# nr1.net
KiCad netlist of a schematic drawn in EAGLE
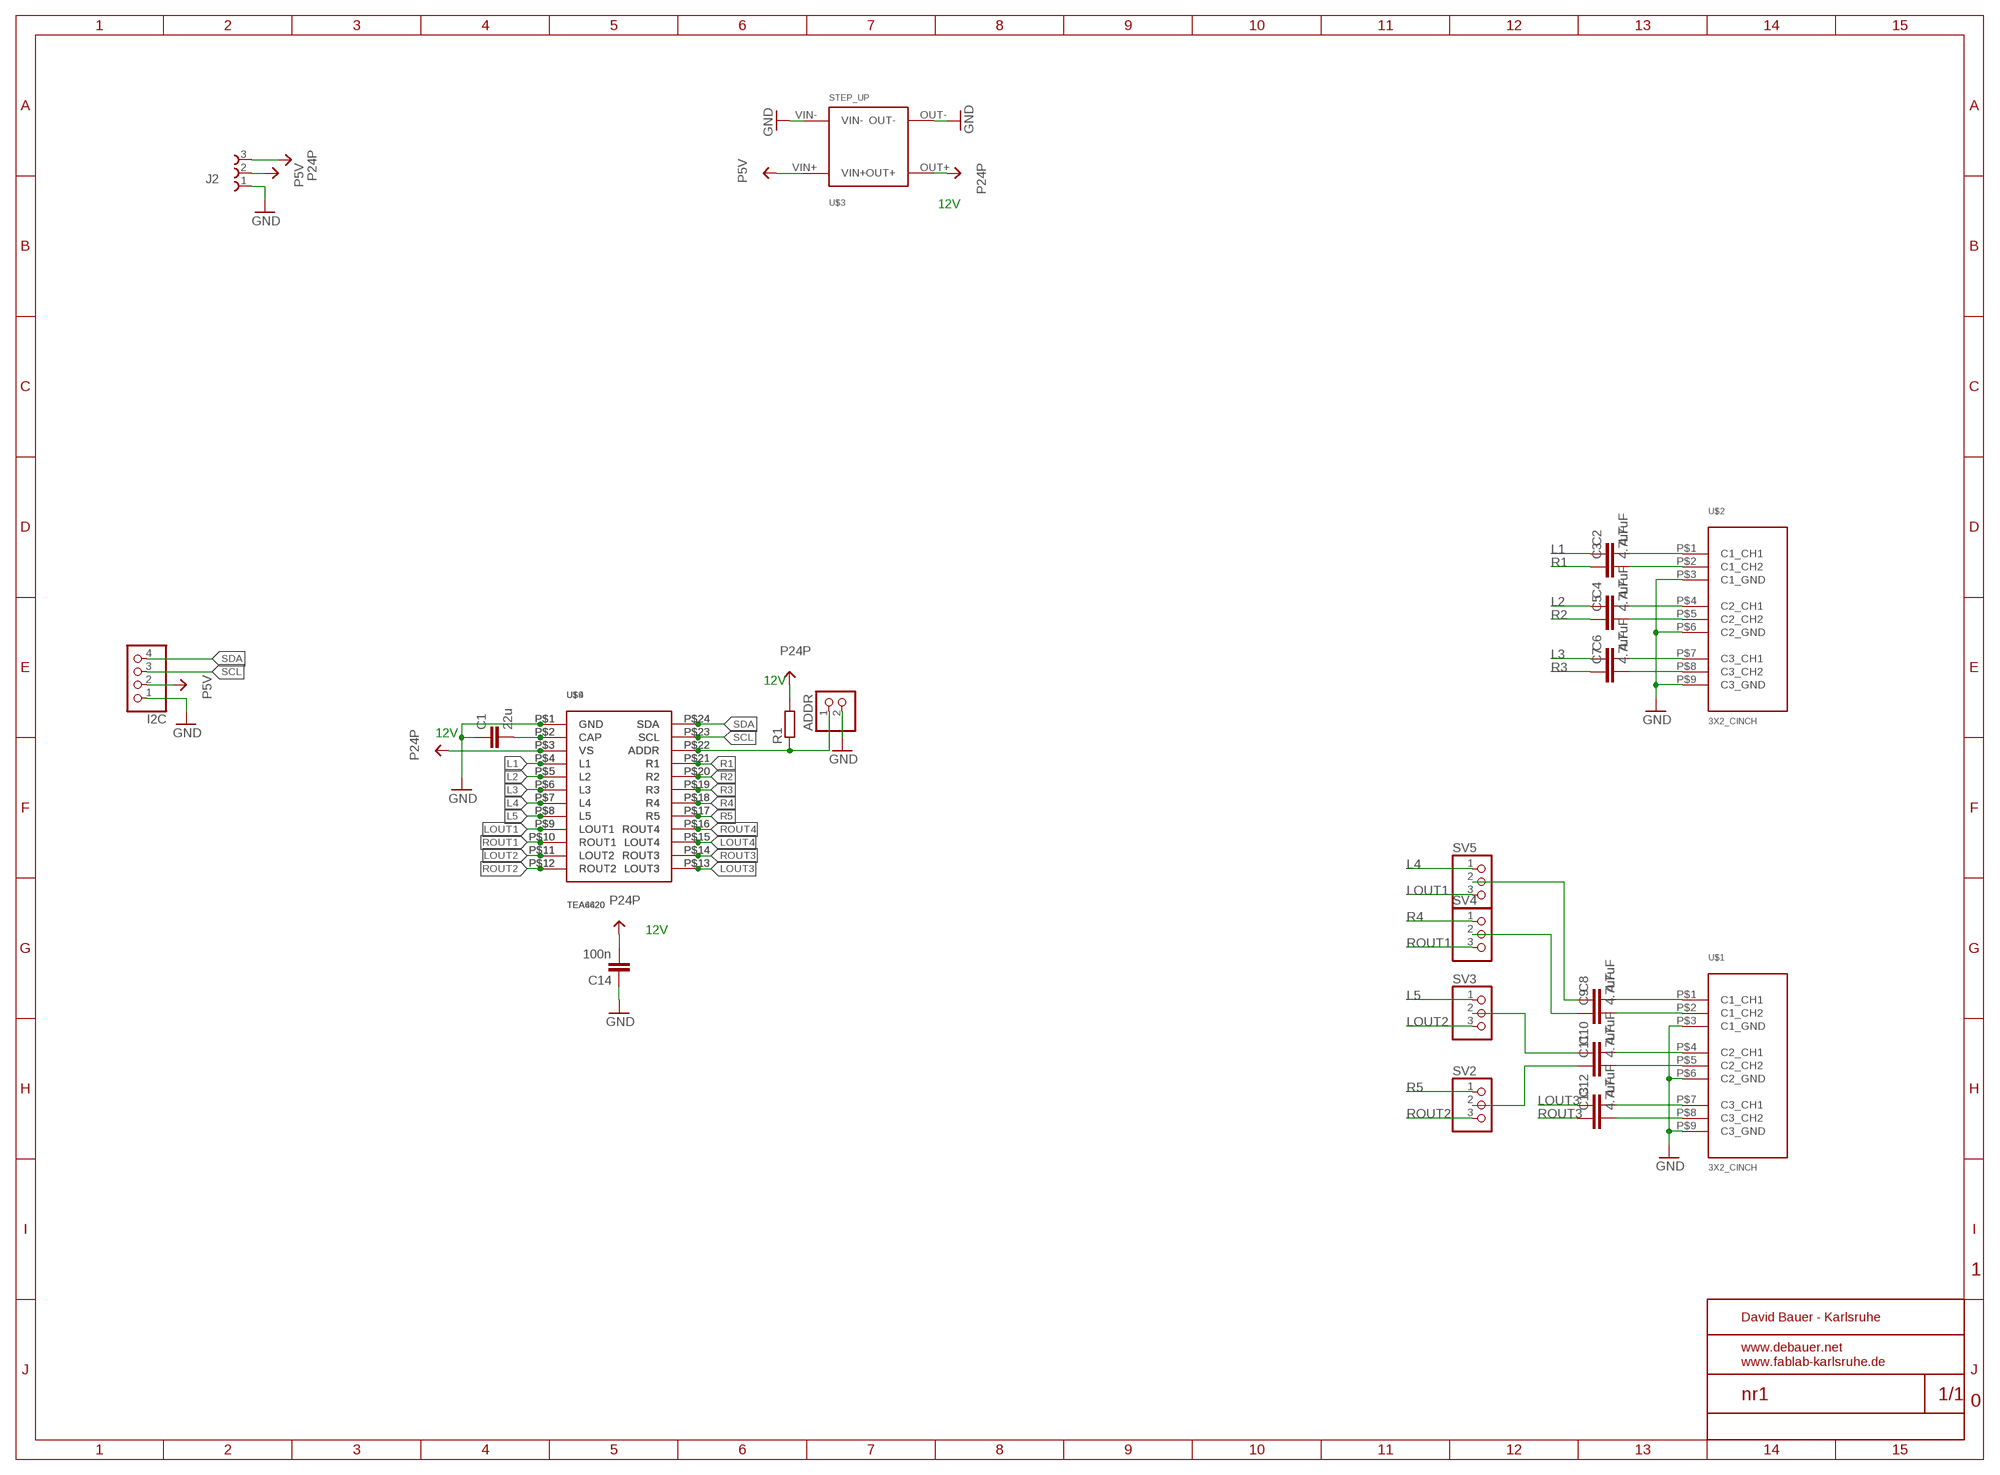
[diagram p0: schematic, sheet 1]

(export (version "E")
  (design (tool "Eeschema 10.0.6"))
  (components
    (comp (ref "ADDR")
      (value "PINHD-1X2")
      (footprint "eagle-import:1X02")
      (libsource (lib "eagle-import") (part "PINHD-1X2"))
    )
    (comp (ref "C1")
      (value "22u")
      (footprint "eagle-import:C0805")
      (libsource (lib "eagle-import") (part "C-EUC0805"))
    )
    (comp (ref "C2")
      (value "4.7uF")
      (footprint "eagle-import:C0805")
      (libsource (lib "eagle-import") (part "C-EUC0805"))
    )
    (comp (ref "C3")
      (value "4.7uF")
      (footprint "eagle-import:C0805")
      (libsource (lib "eagle-import") (part "C-EUC0805"))
    )
    (comp (ref "C4")
      (value "4.7uF")
      (footprint "eagle-import:C0805")
      (libsource (lib "eagle-import") (part "C-EUC0805"))
    )
    (comp (ref "C5")
      (value "4.7uF")
      (footprint "eagle-import:C0805")
      (libsource (lib "eagle-import") (part "C-EUC0805"))
    )
    (comp (ref "C6")
      (value "4.7uF")
      (footprint "eagle-import:C0805")
      (libsource (lib "eagle-import") (part "C-EUC0805"))
    )
    (comp (ref "C7")
      (value "4.7uF")
      (footprint "eagle-import:C0805")
      (libsource (lib "eagle-import") (part "C-EUC0805"))
    )
    (comp (ref "C8")
      (value "4.7uF")
      (footprint "eagle-import:C0805")
      (libsource (lib "eagle-import") (part "C-EUC0805"))
    )
    (comp (ref "C9")
      (value "4.7uF")
      (footprint "eagle-import:C0805")
      (libsource (lib "eagle-import") (part "C-EUC0805"))
    )
    (comp (ref "C10")
      (value "4.7uF")
      (footprint "eagle-import:C0805")
      (libsource (lib "eagle-import") (part "C-EUC0805"))
    )
    (comp (ref "C11")
      (value "4.7uF")
      (footprint "eagle-import:C0805")
      (libsource (lib "eagle-import") (part "C-EUC0805"))
    )
    (comp (ref "C12")
      (value "4.7uF")
      (footprint "eagle-import:C0805")
      (libsource (lib "eagle-import") (part "C-EUC0805"))
    )
    (comp (ref "C13")
      (value "4.7uF")
      (footprint "eagle-import:C0805")
      (libsource (lib "eagle-import") (part "C-EUC0805"))
    )
    (comp (ref "C14")
      (value "100n")
      (footprint "eagle-import:C0805")
      (libsource (lib "eagle-import") (part "C-EUC0805"))
    )
    (comp (ref "I2C")
      (value "PINHD-1X4")
      (footprint "eagle-import:1X04")
      (libsource (lib "eagle-import") (part "PINHD-1X4"))
    )
    (comp (ref "J2")
      (value "691210910003")
      (footprint "eagle-import:691210910003")
      (libsource (lib "eagle-import") (part "691210910003"))
    )
    (comp (ref "R1")
      (value "R-EU_R0805")
      (footprint "eagle-import:R0805")
      (libsource (lib "eagle-import") (part "R-EU_R0805"))
    )
    (comp (ref "SV2")
      (value "PINHD-1X3")
      (footprint "eagle-import:1X03")
      (libsource (lib "eagle-import") (part "PINHD-1X3"))
    )
    (comp (ref "SV3")
      (value "PINHD-1X3")
      (footprint "eagle-import:1X03")
      (libsource (lib "eagle-import") (part "PINHD-1X3"))
    )
    (comp (ref "SV4")
      (value "PINHD-1X3")
      (footprint "eagle-import:1X03")
      (libsource (lib "eagle-import") (part "PINHD-1X3"))
    )
    (comp (ref "SV5")
      (value "PINHD-1X3")
      (footprint "eagle-import:1X03")
      (libsource (lib "eagle-import") (part "PINHD-1X3"))
    )
    (comp (ref "U$1")
      (value "3X2_CINCH")
      (footprint "eagle-import:3X2_CINCH")
      (libsource (lib "eagle-import") (part "3X2_CINCH"))
    )
    (comp (ref "U$2")
      (value "3X2_CINCH")
      (footprint "eagle-import:3X2_CINCH")
      (libsource (lib "eagle-import") (part "3X2_CINCH"))
    )
    (comp (ref "U$3")
      (value "STEP_UP")
      (footprint "eagle-import:STEP_UP")
      (libsource (lib "eagle-import") (part "STEP_UP"))
    )
    (comp (ref "U$4")
      (value "TEA4620")
      (footprint "eagle-import:TEA4620")
      (libsource (lib "eagle-import") (part "TEA4620"))
    )
    (comp (ref "U$9")
      (value "TEA6420")
      (footprint "eagle-import:SHRINK24")
      (libsource (lib "eagle-import") (part "TEA6420"))
    )
  )
  (nets
    (net (code "1") (name "GND") (class "Default")
      (node (ref "ADDR") (pin "2") (pinfunction "2_2") (pintype "passive"))
      (node (ref "C1") (pin "1") (pinfunction "1_1") (pintype "passive"))
      (node (ref "C14") (pin "1") (pinfunction "1_1") (pintype "passive"))
      (node (ref "I2C") (pin "1") (pinfunction "1_1") (pintype "passive"))
      (node (ref "J2") (pin "1") (pinfunction "1_1") (pintype "passive"))
      (node (ref "U$1") (pin "P$3") (pinfunction "C1_GND_P$3") (pintype "bidirectional"))
      (node (ref "U$1") (pin "P$6") (pinfunction "C2_GND_P$6") (pintype "bidirectional"))
      (node (ref "U$1") (pin "P$9") (pinfunction "C3_GND_P$9") (pintype "bidirectional"))
      (node (ref "U$2") (pin "P$3") (pinfunction "C1_GND_P$3") (pintype "bidirectional"))
      (node (ref "U$2") (pin "P$6") (pinfunction "C2_GND_P$6") (pintype "bidirectional"))
      (node (ref "U$2") (pin "P$9") (pinfunction "C3_GND_P$9") (pintype "bidirectional"))
      (node (ref "U$3") (pin "OUT-") (pinfunction "OUT-_OUT-") (pintype "bidirectional"))
      (node (ref "U$3") (pin "VIN-") (pinfunction "VIN-_VIN-") (pintype "bidirectional"))
      (node (ref "U$4") (pin "P$1") (pinfunction "GND_P$1") (pintype "bidirectional"))
      (node (ref "U$9") (pin "P$1") (pinfunction "GND_P$1") (pintype "bidirectional"))
    )
    (net (code "2") (name "L1") (class "Default")
      (node (ref "C2") (pin "1") (pinfunction "1_1") (pintype "passive"))
      (node (ref "U$4") (pin "P$4") (pinfunction "L1_P$4") (pintype "bidirectional"))
      (node (ref "U$9") (pin "P$4") (pinfunction "L1_P$4") (pintype "bidirectional"))
    )
    (net (code "3") (name "L2") (class "Default")
      (node (ref "C4") (pin "1") (pinfunction "1_1") (pintype "passive"))
      (node (ref "U$4") (pin "P$5") (pinfunction "L2_P$5") (pintype "bidirectional"))
      (node (ref "U$9") (pin "P$5") (pinfunction "L2_P$5") (pintype "bidirectional"))
    )
    (net (code "4") (name "L3") (class "Default")
      (node (ref "C6") (pin "1") (pinfunction "1_1") (pintype "passive"))
      (node (ref "U$4") (pin "P$6") (pinfunction "L3_P$6") (pintype "bidirectional"))
      (node (ref "U$9") (pin "P$6") (pinfunction "L3_P$6") (pintype "bidirectional"))
    )
    (net (code "5") (name "L4") (class "Default")
      (node (ref "SV5") (pin "1") (pinfunction "1_1") (pintype "passive"))
      (node (ref "U$4") (pin "P$7") (pinfunction "L4_P$7") (pintype "bidirectional"))
      (node (ref "U$9") (pin "P$7") (pinfunction "L4_P$7") (pintype "bidirectional"))
    )
    (net (code "6") (name "L5") (class "Default")
      (node (ref "SV3") (pin "1") (pinfunction "1_1") (pintype "passive"))
      (node (ref "U$4") (pin "P$8") (pinfunction "L5_P$8") (pintype "bidirectional"))
      (node (ref "U$9") (pin "P$8") (pinfunction "L5_P$8") (pintype "bidirectional"))
    )
    (net (code "7") (name "LOUT1") (class "Default")
      (node (ref "SV5") (pin "3") (pinfunction "3_3") (pintype "passive"))
      (node (ref "U$4") (pin "P$9") (pinfunction "LOUT1_P$9") (pintype "bidirectional"))
      (node (ref "U$9") (pin "P$9") (pinfunction "LOUT1_P$9") (pintype "bidirectional"))
    )
    (net (code "8") (name "LOUT2") (class "Default")
      (node (ref "SV3") (pin "3") (pinfunction "3_3") (pintype "passive"))
      (node (ref "U$4") (pin "P$11") (pinfunction "LOUT2_P$11") (pintype "bidirectional"))
      (node (ref "U$9") (pin "P$11") (pinfunction "LOUT2_P$11") (pintype "bidirectional"))
    )
    (net (code "9") (name "LOUT3") (class "Default")
      (node (ref "C12") (pin "1") (pinfunction "1_1") (pintype "passive"))
      (node (ref "U$4") (pin "P$13") (pinfunction "LOUT3_P$13") (pintype "bidirectional"))
      (node (ref "U$9") (pin "P$13") (pinfunction "LOUT3_P$13") (pintype "bidirectional"))
    )
    (net (code "10") (name "LOUT4") (class "Default")
      (node (ref "U$4") (pin "P$15") (pinfunction "LOUT4_P$15") (pintype "bidirectional"))
      (node (ref "U$9") (pin "P$15") (pinfunction "LOUT4_P$15") (pintype "bidirectional"))
    )
    (net (code "11") (name "Net-(C8-Pad1)") (class "Default")
      (node (ref "C8") (pin "1") (pinfunction "1_1") (pintype "passive"))
      (node (ref "SV5") (pin "2") (pinfunction "2_2") (pintype "passive"))
    )
    (net (code "12") (name "Net-(C9-Pad1)") (class "Default")
      (node (ref "C9") (pin "1") (pinfunction "1_1") (pintype "passive"))
      (node (ref "SV4") (pin "2") (pinfunction "2_2") (pintype "passive"))
    )
    (net (code "13") (name "Net-(C10-Pad1)") (class "Default")
      (node (ref "C10") (pin "1") (pinfunction "1_1") (pintype "passive"))
      (node (ref "SV3") (pin "2") (pinfunction "2_2") (pintype "passive"))
    )
    (net (code "14") (name "Net-(C11-Pad1)") (class "Default")
      (node (ref "C11") (pin "1") (pinfunction "1_1") (pintype "passive"))
      (node (ref "SV2") (pin "2") (pinfunction "2_2") (pintype "passive"))
    )
    (net (code "15") (name "Net-(U$1-C1_CH1)") (class "Default")
      (node (ref "C8") (pin "2") (pinfunction "2_2") (pintype "passive"))
      (node (ref "U$1") (pin "P$1") (pinfunction "C1_CH1_P$1") (pintype "bidirectional"))
    )
    (net (code "16") (name "Net-(U$1-C1_CH2)") (class "Default")
      (node (ref "C9") (pin "2") (pinfunction "2_2") (pintype "passive"))
      (node (ref "U$1") (pin "P$2") (pinfunction "C1_CH2_P$2") (pintype "bidirectional"))
    )
    (net (code "17") (name "Net-(U$1-C2_CH1)") (class "Default")
      (node (ref "C10") (pin "2") (pinfunction "2_2") (pintype "passive"))
      (node (ref "U$1") (pin "P$4") (pinfunction "C2_CH1_P$4") (pintype "bidirectional"))
    )
    (net (code "18") (name "Net-(U$1-C2_CH2)") (class "Default")
      (node (ref "C11") (pin "2") (pinfunction "2_2") (pintype "passive"))
      (node (ref "U$1") (pin "P$5") (pinfunction "C2_CH2_P$5") (pintype "bidirectional"))
    )
    (net (code "19") (name "Net-(U$1-C3_CH1)") (class "Default")
      (node (ref "C12") (pin "2") (pinfunction "2_2") (pintype "passive"))
      (node (ref "U$1") (pin "P$7") (pinfunction "C3_CH1_P$7") (pintype "bidirectional"))
    )
    (net (code "20") (name "Net-(U$1-C3_CH2)") (class "Default")
      (node (ref "C13") (pin "2") (pinfunction "2_2") (pintype "passive"))
      (node (ref "U$1") (pin "P$8") (pinfunction "C3_CH2_P$8") (pintype "bidirectional"))
    )
    (net (code "21") (name "Net-(U$2-C1_CH1)") (class "Default")
      (node (ref "C2") (pin "2") (pinfunction "2_2") (pintype "passive"))
      (node (ref "U$2") (pin "P$1") (pinfunction "C1_CH1_P$1") (pintype "bidirectional"))
    )
    (net (code "22") (name "Net-(U$2-C1_CH2)") (class "Default")
      (node (ref "C3") (pin "2") (pinfunction "2_2") (pintype "passive"))
      (node (ref "U$2") (pin "P$2") (pinfunction "C1_CH2_P$2") (pintype "bidirectional"))
    )
    (net (code "23") (name "Net-(U$2-C2_CH1)") (class "Default")
      (node (ref "C4") (pin "2") (pinfunction "2_2") (pintype "passive"))
      (node (ref "U$2") (pin "P$4") (pinfunction "C2_CH1_P$4") (pintype "bidirectional"))
    )
    (net (code "24") (name "Net-(U$2-C2_CH2)") (class "Default")
      (node (ref "C5") (pin "2") (pinfunction "2_2") (pintype "passive"))
      (node (ref "U$2") (pin "P$5") (pinfunction "C2_CH2_P$5") (pintype "bidirectional"))
    )
    (net (code "25") (name "Net-(U$2-C3_CH1)") (class "Default")
      (node (ref "C6") (pin "2") (pinfunction "2_2") (pintype "passive"))
      (node (ref "U$2") (pin "P$7") (pinfunction "C3_CH1_P$7") (pintype "bidirectional"))
    )
    (net (code "26") (name "Net-(U$2-C3_CH2)") (class "Default")
      (node (ref "C7") (pin "2") (pinfunction "2_2") (pintype "passive"))
      (node (ref "U$2") (pin "P$8") (pinfunction "C3_CH2_P$8") (pintype "bidirectional"))
    )
    (net (code "27") (name "Net-(U$4-ADDR)") (class "Default")
      (node (ref "ADDR") (pin "1") (pinfunction "1_1") (pintype "passive"))
      (node (ref "R1") (pin "1") (pinfunction "1_1") (pintype "passive"))
      (node (ref "U$4") (pin "P$22") (pinfunction "ADDR_P$22") (pintype "bidirectional"))
      (node (ref "U$9") (pin "P$22") (pinfunction "ADDR_P$22") (pintype "bidirectional"))
    )
    (net (code "28") (name "Net-(U$4-CAP)") (class "Default")
      (node (ref "C1") (pin "2") (pinfunction "2_2") (pintype "passive"))
      (node (ref "U$4") (pin "P$2") (pinfunction "CAP_P$2") (pintype "bidirectional"))
      (node (ref "U$9") (pin "P$2") (pinfunction "CAP_P$2") (pintype "bidirectional"))
    )
    (net (code "29") (name "P5V") (class "Default")
      (node (ref "I2C") (pin "2") (pinfunction "2_2") (pintype "passive"))
      (node (ref "J2") (pin "2") (pinfunction "2_2") (pintype "passive"))
      (node (ref "U$3") (pin "VIN+") (pinfunction "VIN+_VIN+") (pintype "bidirectional"))
    )
    (net (code "30") (name "P24P") (class "Default")
      (node (ref "C14") (pin "2") (pinfunction "2_2") (pintype "passive"))
      (node (ref "J2") (pin "3") (pinfunction "3_3") (pintype "passive"))
      (node (ref "R1") (pin "2") (pinfunction "2_2") (pintype "passive"))
      (node (ref "U$3") (pin "OUT+") (pinfunction "OUT+_OUT+") (pintype "bidirectional"))
      (node (ref "U$4") (pin "P$3") (pinfunction "VS_P$3") (pintype "bidirectional"))
      (node (ref "U$9") (pin "P$3") (pinfunction "VS_P$3") (pintype "bidirectional"))
    )
    (net (code "31") (name "R1") (class "Default")
      (node (ref "C3") (pin "1") (pinfunction "1_1") (pintype "passive"))
      (node (ref "U$4") (pin "P$21") (pinfunction "R1_P$21") (pintype "bidirectional"))
      (node (ref "U$9") (pin "P$21") (pinfunction "R1_P$21") (pintype "bidirectional"))
    )
    (net (code "32") (name "R2") (class "Default")
      (node (ref "C5") (pin "1") (pinfunction "1_1") (pintype "passive"))
      (node (ref "U$4") (pin "P$20") (pinfunction "R2_P$20") (pintype "bidirectional"))
      (node (ref "U$9") (pin "P$20") (pinfunction "R2_P$20") (pintype "bidirectional"))
    )
    (net (code "33") (name "R3") (class "Default")
      (node (ref "C7") (pin "1") (pinfunction "1_1") (pintype "passive"))
      (node (ref "U$4") (pin "P$19") (pinfunction "R3_P$19") (pintype "bidirectional"))
      (node (ref "U$9") (pin "P$19") (pinfunction "R3_P$19") (pintype "bidirectional"))
    )
    (net (code "34") (name "R4") (class "Default")
      (node (ref "SV4") (pin "1") (pinfunction "1_1") (pintype "passive"))
      (node (ref "U$4") (pin "P$18") (pinfunction "R4_P$18") (pintype "bidirectional"))
      (node (ref "U$9") (pin "P$18") (pinfunction "R4_P$18") (pintype "bidirectional"))
    )
    (net (code "35") (name "R5") (class "Default")
      (node (ref "SV2") (pin "1") (pinfunction "1_1") (pintype "passive"))
      (node (ref "U$4") (pin "P$17") (pinfunction "R5_P$17") (pintype "bidirectional"))
      (node (ref "U$9") (pin "P$17") (pinfunction "R5_P$17") (pintype "bidirectional"))
    )
    (net (code "36") (name "ROUT1") (class "Default")
      (node (ref "SV4") (pin "3") (pinfunction "3_3") (pintype "passive"))
      (node (ref "U$4") (pin "P$10") (pinfunction "ROUT1_P$10") (pintype "bidirectional"))
      (node (ref "U$9") (pin "P$10") (pinfunction "ROUT1_P$10") (pintype "bidirectional"))
    )
    (net (code "37") (name "ROUT2") (class "Default")
      (node (ref "SV2") (pin "3") (pinfunction "3_3") (pintype "passive"))
      (node (ref "U$4") (pin "P$12") (pinfunction "ROUT2_P$12") (pintype "bidirectional"))
      (node (ref "U$9") (pin "P$12") (pinfunction "ROUT2_P$12") (pintype "bidirectional"))
    )
    (net (code "38") (name "ROUT3") (class "Default")
      (node (ref "C13") (pin "1") (pinfunction "1_1") (pintype "passive"))
      (node (ref "U$4") (pin "P$14") (pinfunction "ROUT3_P$14") (pintype "bidirectional"))
      (node (ref "U$9") (pin "P$14") (pinfunction "ROUT3_P$14") (pintype "bidirectional"))
    )
    (net (code "39") (name "ROUT4") (class "Default")
      (node (ref "U$4") (pin "P$16") (pinfunction "ROUT4_P$16") (pintype "bidirectional"))
      (node (ref "U$9") (pin "P$16") (pinfunction "ROUT4_P$16") (pintype "bidirectional"))
    )
    (net (code "40") (name "SCL") (class "Default")
      (node (ref "I2C") (pin "3") (pinfunction "3_3") (pintype "passive"))
      (node (ref "U$4") (pin "P$23") (pinfunction "SCL_P$23") (pintype "bidirectional"))
      (node (ref "U$9") (pin "P$23") (pinfunction "SCL_P$23") (pintype "bidirectional"))
    )
    (net (code "41") (name "SDA") (class "Default")
      (node (ref "I2C") (pin "4") (pinfunction "4_4") (pintype "passive"))
      (node (ref "U$4") (pin "P$24") (pinfunction "SDA_P$24") (pintype "bidirectional"))
      (node (ref "U$9") (pin "P$24") (pinfunction "SDA_P$24") (pintype "bidirectional"))
    )
  )
)
